# HackHarder.net
KiCad netlist of a schematic drawn in EAGLE
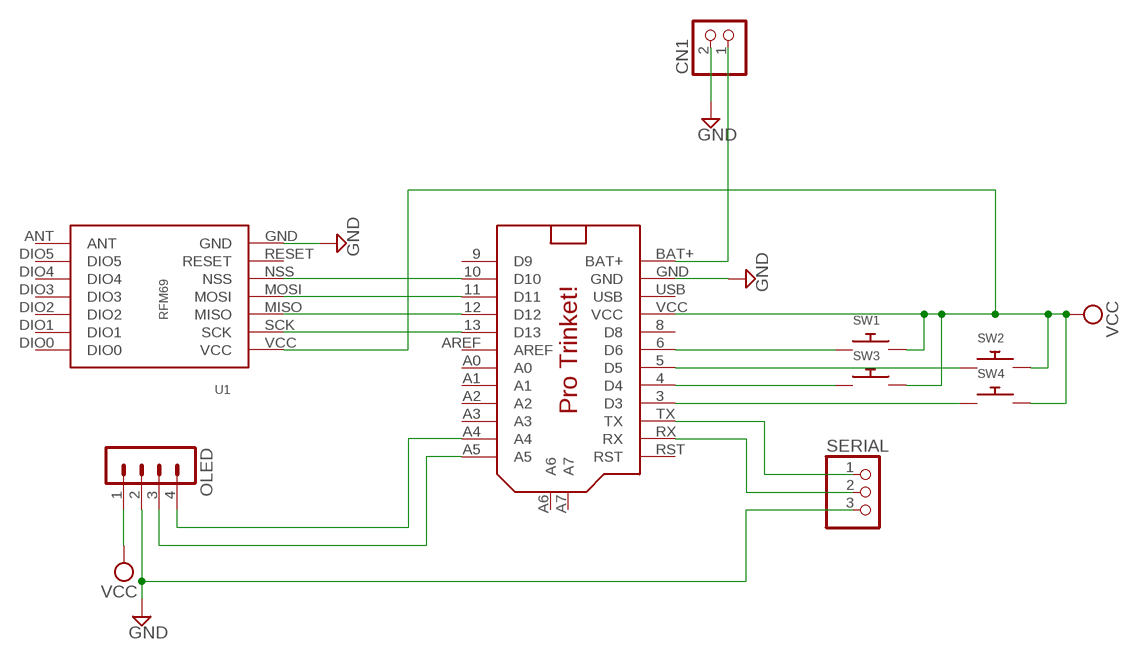
[diagram p0: schematic, sheet 1]

(export (version "E")
  (design (tool "Eeschema 10.0.6"))
  (components
    (comp (ref "CN1")
      (value "JST_2PIN-SMT-RA")
      (footprint "eagle-import:JST-PH-2-SMT-RA")
      (libsource (lib "eagle-import") (part "JST_2PIN-SMT-RA"))
    )
    (comp (ref "MCU1")
      (value "PRO_TRINKET")
      (footprint "eagle-import:PROTRINKET")
      (libsource (lib "eagle-import") (part "PRO_TRINKET"))
    )
    (comp (ref "OLED")
      (value "MA04-1")
      (footprint "eagle-import:MA04-1")
      (libsource (lib "eagle-import") (part "MA04-1"))
    )
    (comp (ref "SERIAL")
      (value "PINHD-1X3")
      (footprint "eagle-import:1X03")
      (libsource (lib "eagle-import") (part "PINHD-1X3"))
    )
    (comp (ref "SW1")
      (value "SWITCH_PUSHBUTTONEVQ-PE")
      (footprint "eagle-import:TACT_PANA-EVQ")
      (libsource (lib "eagle-import") (part "SWITCH_PUSHBUTTONEVQ-PE"))
    )
    (comp (ref "SW2")
      (value "SWITCH_PUSHBUTTONEVQ-PE")
      (footprint "eagle-import:TACT_PANA-EVQ")
      (libsource (lib "eagle-import") (part "SWITCH_PUSHBUTTONEVQ-PE"))
    )
    (comp (ref "SW3")
      (value "SWITCH_PUSHBUTTONEVQ-PE")
      (footprint "eagle-import:TACT_PANA-EVQ")
      (libsource (lib "eagle-import") (part "SWITCH_PUSHBUTTONEVQ-PE"))
    )
    (comp (ref "SW4")
      (value "SWITCH_PUSHBUTTONEVQ-PE")
      (footprint "eagle-import:TACT_PANA-EVQ")
      (libsource (lib "eagle-import") (part "SWITCH_PUSHBUTTONEVQ-PE"))
    )
    (comp (ref "U1")
      (value "RFM69HW")
      (footprint "eagle-import:RFM69_PADS")
      (libsource (lib "eagle-import") (part "RFM69HW"))
    )
  )
  (nets
    (net (code "1") (name "/USB") (class "Default")
      (node (ref "MCU1") (pin "USB") (pinfunction "USB_USB") (pintype "power_in"))
    )
    (net (code "2") (name "GND") (class "Default")
      (node (ref "CN1") (pin "2") (pinfunction "1_2") (pintype "passive"))
      (node (ref "MCU1") (pin "GND") (pinfunction "GND_GND") (pintype "power_in"))
      (node (ref "OLED") (pin "2") (pinfunction "2_2") (pintype "passive"))
      (node (ref "SERIAL") (pin "3") (pinfunction "3_3") (pintype "passive"))
      (node (ref "U1") (pin "GND") (pinfunction "GND_GND") (pintype "bidirectional"))
    )
    (net (code "3") (name "Net-(CN1-2)") (class "Default")
      (node (ref "CN1") (pin "1") (pinfunction "2_1") (pintype "passive"))
      (node (ref "MCU1") (pin "BAT+") (pinfunction "BAT+_BAT+") (pintype "power_in"))
    )
    (net (code "4") (name "Net-(MCU1-D3)") (class "Default")
      (node (ref "MCU1") (pin "3") (pinfunction "D3_3") (pintype "bidirectional"))
      (node (ref "SW4") (pin "P$1") (pinfunction "P$1_P$1") (pintype "passive"))
    )
    (net (code "5") (name "Net-(MCU1-D4)") (class "Default")
      (node (ref "MCU1") (pin "4") (pinfunction "D4_4") (pintype "bidirectional"))
      (node (ref "SW3") (pin "P$1") (pinfunction "P$1_P$1") (pintype "passive"))
    )
    (net (code "6") (name "Net-(MCU1-D5)") (class "Default")
      (node (ref "MCU1") (pin "5") (pinfunction "D5_5") (pintype "bidirectional"))
      (node (ref "SW2") (pin "P$1") (pinfunction "P$1_P$1") (pintype "passive"))
    )
    (net (code "7") (name "Net-(MCU1-D6)") (class "Default")
      (node (ref "MCU1") (pin "6") (pinfunction "D6_6") (pintype "bidirectional"))
      (node (ref "SW1") (pin "P$1") (pinfunction "P$1_P$1") (pintype "passive"))
    )
    (net (code "8") (name "Net-(MCU1-D10)") (class "Default")
      (node (ref "MCU1") (pin "10") (pinfunction "D10_10") (pintype "bidirectional"))
      (node (ref "U1") (pin "NSS") (pinfunction "NSS_NSS") (pintype "bidirectional"))
    )
    (net (code "9") (name "Net-(MCU1-D11)") (class "Default")
      (node (ref "MCU1") (pin "11") (pinfunction "D11_11") (pintype "bidirectional"))
      (node (ref "U1") (pin "MOSI") (pinfunction "MOSI_MOSI") (pintype "bidirectional"))
    )
    (net (code "10") (name "Net-(MCU1-D12)") (class "Default")
      (node (ref "MCU1") (pin "12") (pinfunction "D12_12") (pintype "bidirectional"))
      (node (ref "U1") (pin "MISO") (pinfunction "MISO_MISO") (pintype "bidirectional"))
    )
    (net (code "11") (name "Net-(MCU1-D13)") (class "Default")
      (node (ref "MCU1") (pin "13") (pinfunction "D13_13") (pintype "bidirectional"))
      (node (ref "U1") (pin "SCK") (pinfunction "SCK_SCK") (pintype "bidirectional"))
    )
    (net (code "12") (name "Net-(MCU1-PadA4)") (class "Default")
      (node (ref "MCU1") (pin "A4") (pinfunction "A4_A4") (pintype "bidirectional"))
      (node (ref "OLED") (pin "4") (pinfunction "4_4") (pintype "passive"))
    )
    (net (code "13") (name "Net-(MCU1-PadA5)") (class "Default")
      (node (ref "MCU1") (pin "A5") (pinfunction "A5_A5") (pintype "bidirectional"))
      (node (ref "OLED") (pin "3") (pinfunction "3_3") (pintype "passive"))
    )
    (net (code "14") (name "Net-(MCU1-PadRX)") (class "Default")
      (node (ref "MCU1") (pin "RX") (pinfunction "RX_RX") (pintype "bidirectional"))
      (node (ref "SERIAL") (pin "2") (pinfunction "2_2") (pintype "passive"))
    )
    (net (code "15") (name "Net-(MCU1-PadTX)") (class "Default")
      (node (ref "MCU1") (pin "TX") (pinfunction "TX_TX") (pintype "bidirectional"))
      (node (ref "SERIAL") (pin "1") (pinfunction "1_1") (pintype "passive"))
    )
    (net (code "16") (name "VCC") (class "Default")
      (node (ref "MCU1") (pin "VCC") (pinfunction "VCC_VCC") (pintype "power_in"))
      (node (ref "OLED") (pin "1") (pinfunction "1_1") (pintype "passive"))
      (node (ref "SW1") (pin "P$2") (pinfunction "P$2_P$2") (pintype "passive"))
      (node (ref "SW2") (pin "P$2") (pinfunction "P$2_P$2") (pintype "passive"))
      (node (ref "SW3") (pin "P$2") (pinfunction "P$2_P$2") (pintype "passive"))
      (node (ref "SW4") (pin "P$2") (pinfunction "P$2_P$2") (pintype "passive"))
      (node (ref "U1") (pin "VCC") (pinfunction "VCC_VCC") (pintype "bidirectional"))
    )
    (net (code "17") (name "unconnected-(MCU1-D8-Pad8)") (class "Default")
      (node (ref "MCU1") (pin "8") (pinfunction "D8_8") (pintype "bidirectional"))
    )
    (net (code "18") (name "unconnected-(MCU1-D9-Pad9)") (class "Default")
      (node (ref "MCU1") (pin "9") (pinfunction "D9_9") (pintype "bidirectional"))
    )
    (net (code "19") (name "unconnected-(MCU1-PadA0)") (class "Default")
      (node (ref "MCU1") (pin "A0") (pinfunction "A0_A0") (pintype "bidirectional"))
    )
    (net (code "20") (name "unconnected-(MCU1-PadA1)") (class "Default")
      (node (ref "MCU1") (pin "A1") (pinfunction "A1_A1") (pintype "bidirectional"))
    )
    (net (code "21") (name "unconnected-(MCU1-PadA2)") (class "Default")
      (node (ref "MCU1") (pin "A2") (pinfunction "A2_A2") (pintype "bidirectional"))
    )
    (net (code "22") (name "unconnected-(MCU1-PadA3)") (class "Default")
      (node (ref "MCU1") (pin "A3") (pinfunction "A3_A3") (pintype "bidirectional"))
    )
    (net (code "23") (name "unconnected-(MCU1-PadA6)") (class "Default")
      (node (ref "MCU1") (pin "A6") (pinfunction "A6_A6") (pintype "passive"))
    )
    (net (code "24") (name "unconnected-(MCU1-PadA7)") (class "Default")
      (node (ref "MCU1") (pin "A7") (pinfunction "A7_A7") (pintype "passive"))
    )
    (net (code "25") (name "unconnected-(MCU1-PadAREF)") (class "Default")
      (node (ref "MCU1") (pin "AREF") (pinfunction "AREF_AREF") (pintype "passive"))
    )
    (net (code "26") (name "unconnected-(MCU1-PadRST)") (class "Default")
      (node (ref "MCU1") (pin "RST") (pinfunction "RST_RST") (pintype "passive"))
    )
    (net (code "27") (name "unconnected-(U1-PadANT)") (class "Default")
      (node (ref "U1") (pin "ANT") (pinfunction "ANT_ANT") (pintype "bidirectional"))
    )
    (net (code "28") (name "unconnected-(U1-PadDIO0)") (class "Default")
      (node (ref "U1") (pin "DIO0") (pinfunction "DIO0_DIO0") (pintype "bidirectional"))
    )
    (net (code "29") (name "unconnected-(U1-PadDIO1)") (class "Default")
      (node (ref "U1") (pin "DIO1") (pinfunction "DIO1_DIO1") (pintype "bidirectional"))
    )
    (net (code "30") (name "unconnected-(U1-PadDIO2)") (class "Default")
      (node (ref "U1") (pin "DIO2") (pinfunction "DIO2_DIO2") (pintype "bidirectional"))
    )
    (net (code "31") (name "unconnected-(U1-PadDIO3)") (class "Default")
      (node (ref "U1") (pin "DIO3") (pinfunction "DIO3_DIO3") (pintype "bidirectional"))
    )
    (net (code "32") (name "unconnected-(U1-PadDIO4)") (class "Default")
      (node (ref "U1") (pin "DIO4") (pinfunction "DIO4_DIO4") (pintype "bidirectional"))
    )
    (net (code "33") (name "unconnected-(U1-PadDIO5)") (class "Default")
      (node (ref "U1") (pin "DIO5") (pinfunction "DIO5_DIO5") (pintype "bidirectional"))
    )
    (net (code "34") (name "unconnected-(U1-PadRESET)") (class "Default")
      (node (ref "U1") (pin "RESET") (pinfunction "RESET_RESET") (pintype "bidirectional"))
    )
  )
)
